# Port_Expander_for_Plug_and_Play.net
KiCad netlist of a schematic drawn in EAGLE
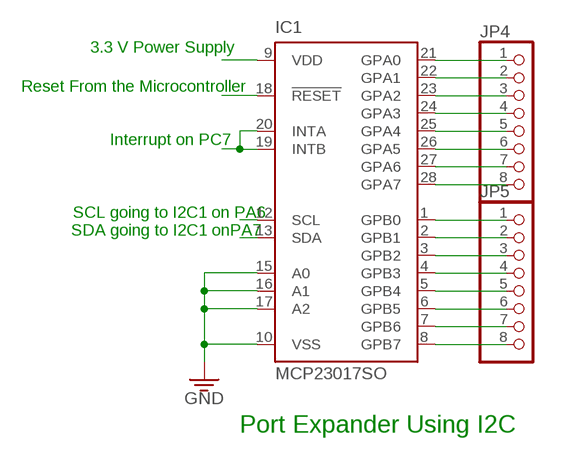
[diagram p0: schematic, sheet 1]

(export (version "E")
  (design (tool "Eeschema 10.0.6"))
  (components
    (comp (ref "IC1")
      (value "MCP23017SO")
      (footprint "eagle-import:SO28W")
      (libsource (lib "eagle-import") (part "MCP23017SO"))
    )
    (comp (ref "JP4")
      (value "PINHD-1X8BIG")
      (footprint "eagle-import:1X08-BIG")
      (libsource (lib "eagle-import") (part "PINHD-1X8BIG"))
    )
    (comp (ref "JP5")
      (value "PINHD-1X8BIG")
      (footprint "eagle-import:1X08-BIG")
      (libsource (lib "eagle-import") (part "PINHD-1X8BIG"))
    )
  )
  (nets
    (net (code "1") (name "GND") (class "Default")
      (node (ref "IC1") (pin "10") (pinfunction "VSS_10") (pintype "power_in"))
      (node (ref "IC1") (pin "15") (pinfunction "A0_15") (pintype "input"))
      (node (ref "IC1") (pin "16") (pinfunction "A1_16") (pintype "input"))
      (node (ref "IC1") (pin "17") (pinfunction "A2_17") (pintype "input"))
      (node (ref "IC1") (pin "9") (pinfunction "VDD_9") (pintype "power_in"))
    )
    (net (code "2") (name "Net-(IC1-GPA0)") (class "Default")
      (node (ref "IC1") (pin "21") (pinfunction "GPA0_21") (pintype "bidirectional"))
      (node (ref "JP4") (pin "1") (pinfunction "1_1") (pintype "passive"))
    )
    (net (code "3") (name "Net-(IC1-GPA1)") (class "Default")
      (node (ref "IC1") (pin "22") (pinfunction "GPA1_22") (pintype "bidirectional"))
      (node (ref "JP4") (pin "2") (pinfunction "2_2") (pintype "passive"))
    )
    (net (code "4") (name "Net-(IC1-GPA2)") (class "Default")
      (node (ref "IC1") (pin "23") (pinfunction "GPA2_23") (pintype "bidirectional"))
      (node (ref "JP4") (pin "3") (pinfunction "3_3") (pintype "passive"))
    )
    (net (code "5") (name "Net-(IC1-GPA3)") (class "Default")
      (node (ref "IC1") (pin "24") (pinfunction "GPA3_24") (pintype "bidirectional"))
      (node (ref "JP4") (pin "4") (pinfunction "4_4") (pintype "passive"))
    )
    (net (code "6") (name "Net-(IC1-GPA4)") (class "Default")
      (node (ref "IC1") (pin "25") (pinfunction "GPA4_25") (pintype "bidirectional"))
      (node (ref "JP4") (pin "5") (pinfunction "5_5") (pintype "passive"))
    )
    (net (code "7") (name "Net-(IC1-GPA5)") (class "Default")
      (node (ref "IC1") (pin "26") (pinfunction "GPA5_26") (pintype "bidirectional"))
      (node (ref "JP4") (pin "6") (pinfunction "6_6") (pintype "passive"))
    )
    (net (code "8") (name "Net-(IC1-GPA6)") (class "Default")
      (node (ref "IC1") (pin "27") (pinfunction "GPA6_27") (pintype "bidirectional"))
      (node (ref "JP4") (pin "7") (pinfunction "7_7") (pintype "passive"))
    )
    (net (code "9") (name "Net-(IC1-GPA7)") (class "Default")
      (node (ref "IC1") (pin "28") (pinfunction "GPA7_28") (pintype "bidirectional"))
      (node (ref "JP4") (pin "8") (pinfunction "8_8") (pintype "passive"))
    )
    (net (code "10") (name "Net-(IC1-GPB0)") (class "Default")
      (node (ref "IC1") (pin "1") (pinfunction "GPB0_1") (pintype "bidirectional"))
      (node (ref "JP5") (pin "1") (pinfunction "1_1") (pintype "passive"))
    )
    (net (code "11") (name "Net-(IC1-GPB1)") (class "Default")
      (node (ref "IC1") (pin "2") (pinfunction "GPB1_2") (pintype "bidirectional"))
      (node (ref "JP5") (pin "2") (pinfunction "2_2") (pintype "passive"))
    )
    (net (code "12") (name "Net-(IC1-GPB2)") (class "Default")
      (node (ref "IC1") (pin "3") (pinfunction "GPB2_3") (pintype "bidirectional"))
      (node (ref "JP5") (pin "3") (pinfunction "3_3") (pintype "passive"))
    )
    (net (code "13") (name "Net-(IC1-GPB3)") (class "Default")
      (node (ref "IC1") (pin "4") (pinfunction "GPB3_4") (pintype "bidirectional"))
      (node (ref "JP5") (pin "4") (pinfunction "4_4") (pintype "passive"))
    )
    (net (code "14") (name "Net-(IC1-GPB4)") (class "Default")
      (node (ref "IC1") (pin "5") (pinfunction "GPB4_5") (pintype "bidirectional"))
      (node (ref "JP5") (pin "5") (pinfunction "5_5") (pintype "passive"))
    )
    (net (code "15") (name "Net-(IC1-GPB5)") (class "Default")
      (node (ref "IC1") (pin "6") (pinfunction "GPB5_6") (pintype "bidirectional"))
      (node (ref "JP5") (pin "6") (pinfunction "6_6") (pintype "passive"))
    )
    (net (code "16") (name "Net-(IC1-GPB6)") (class "Default")
      (node (ref "IC1") (pin "7") (pinfunction "GPB6_7") (pintype "bidirectional"))
      (node (ref "JP5") (pin "7") (pinfunction "7_7") (pintype "passive"))
    )
    (net (code "17") (name "Net-(IC1-GPB7)") (class "Default")
      (node (ref "IC1") (pin "8") (pinfunction "GPB7_8") (pintype "bidirectional"))
      (node (ref "JP5") (pin "8") (pinfunction "8_8") (pintype "passive"))
    )
    (net (code "18") (name "Net-(IC1-INTA)") (class "Default")
      (node (ref "IC1") (pin "19") (pinfunction "INTB_19") (pintype "output"))
      (node (ref "IC1") (pin "20") (pinfunction "INTA_20") (pintype "output"))
    )
    (net (code "19") (name "unconnected-(IC1-SCL-Pad12)") (class "Default")
      (node (ref "IC1") (pin "12") (pinfunction "SCL_12") (pintype "input"))
    )
    (net (code "20") (name "unconnected-(IC1-SDA-Pad13)") (class "Default")
      (node (ref "IC1") (pin "13") (pinfunction "SDA_13") (pintype "bidirectional"))
    )
    (net (code "21") (name "unconnected-(IC1-~{RESET}-Pad18)") (class "Default")
      (node (ref "IC1") (pin "18") (pinfunction "~{RESET}_18") (pintype "input"))
    )
  )
)
